# design.net
KiCad netlist of a schematic drawn in EAGLE
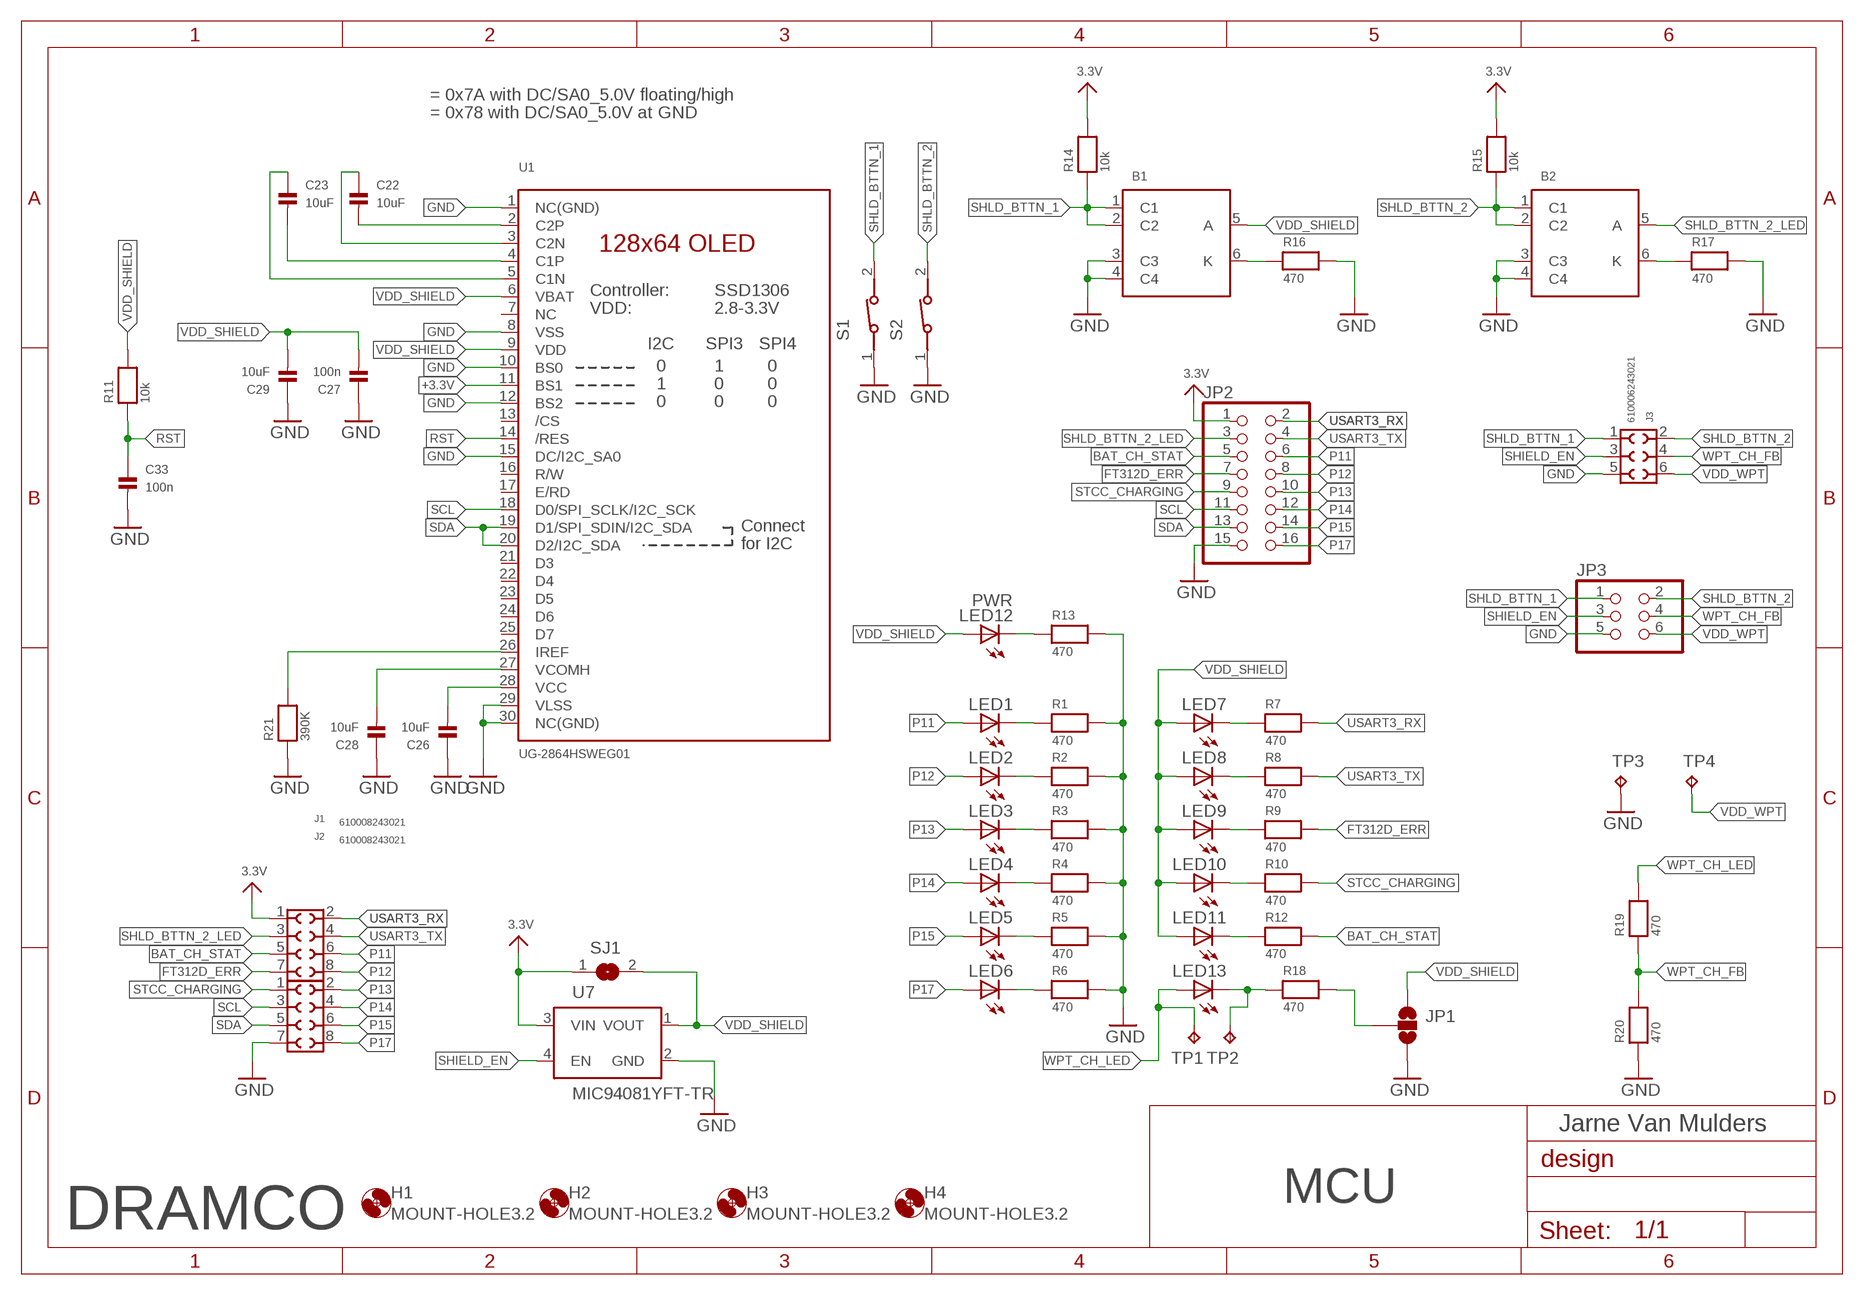
[diagram p0: schematic, sheet 1]

(export (version "E")
  (design (tool "Eeschema 10.0.6"))
  (components
    (comp (ref "B1")
      (value "TS121273")
      (footprint "eagle-import:TS121273")
      (libsource (lib "eagle-import") (part "TS121273"))
    )
    (comp (ref "B2")
      (value "TS121273")
      (footprint "eagle-import:TS121273")
      (libsource (lib "eagle-import") (part "TS121273"))
    )
    (comp (ref "C22")
      (value "10uF")
      (footprint "eagle-import:0805")
      (libsource (lib "eagle-import") (part "CAP_CERAMIC0805"))
    )
    (comp (ref "C23")
      (value "10uF")
      (footprint "eagle-import:0805")
      (libsource (lib "eagle-import") (part "CAP_CERAMIC0805"))
    )
    (comp (ref "C26")
      (value "10uF")
      (footprint "eagle-import:0805")
      (libsource (lib "eagle-import") (part "CAP_CERAMIC0805"))
    )
    (comp (ref "C27")
      (value "100n")
      (footprint "eagle-import:0603")
      (libsource (lib "eagle-import") (part "CAP_CERAMIC0603"))
    )
    (comp (ref "C28")
      (value "10uF")
      (footprint "eagle-import:0805")
      (libsource (lib "eagle-import") (part "CAP_CERAMIC0805"))
    )
    (comp (ref "C29")
      (value "10uF")
      (footprint "eagle-import:0805")
      (libsource (lib "eagle-import") (part "CAP_CERAMIC0805"))
    )
    (comp (ref "C33")
      (value "100n")
      (footprint "eagle-import:0603")
      (libsource (lib "eagle-import") (part "CAP_CERAMIC0603"))
    )
    (comp (ref "H1")
      (value "MOUNT-HOLE3.2")
      (footprint "eagle-import:3,2")
      (libsource (lib "eagle-import") (part "MOUNT-HOLE3.2"))
    )
    (comp (ref "H2")
      (value "MOUNT-HOLE3.2")
      (footprint "eagle-import:3,2")
      (libsource (lib "eagle-import") (part "MOUNT-HOLE3.2"))
    )
    (comp (ref "H3")
      (value "MOUNT-HOLE3.2")
      (footprint "eagle-import:3,2")
      (libsource (lib "eagle-import") (part "MOUNT-HOLE3.2"))
    )
    (comp (ref "H4")
      (value "MOUNT-HOLE3.2")
      (footprint "eagle-import:3,2")
      (libsource (lib "eagle-import") (part "MOUNT-HOLE3.2"))
    )
    (comp (ref "J1")
      (value "610008243021")
      (footprint "eagle-import:610008243021")
      (libsource (lib "eagle-import") (part "6100XX243021_610008243021"))
    )
    (comp (ref "J2")
      (value "610008243021")
      (footprint "eagle-import:610008243021")
      (libsource (lib "eagle-import") (part "6100XX243021_610008243021"))
    )
    (comp (ref "J3")
      (value "610006243021")
      (footprint "eagle-import:610006243021")
      (libsource (lib "eagle-import") (part "6100XX243021_610006243021"))
    )
    (comp (ref "JP1")
      (value "JUMPER-SMT_3_NO_NO-SILK")
      (footprint "eagle-import:SMT-JUMPER_3_NO_NO-SILK")
      (libsource (lib "eagle-import") (part "JUMPER-SMT_3_NO_NO-SILK"))
    )
    (comp (ref "JP2")
      (value "HEADER-2X8")
      (footprint "eagle-import:2X08")
      (libsource (lib "eagle-import") (part "HEADER-2X8"))
    )
    (comp (ref "JP3")
      (value "HEADER-2X3")
      (footprint "eagle-import:2X03_ROUND_70MIL")
      (libsource (lib "eagle-import") (part "HEADER-2X3"))
    )
    (comp (ref "LED1")
      (value "LED3MM")
      (footprint "eagle-import:LED3MM")
      (libsource (lib "eagle-import") (part "LED3MM"))
    )
    (comp (ref "LED2")
      (value "LED3MM")
      (footprint "eagle-import:LED3MM")
      (libsource (lib "eagle-import") (part "LED3MM"))
    )
    (comp (ref "LED3")
      (value "LED3MM")
      (footprint "eagle-import:LED3MM")
      (libsource (lib "eagle-import") (part "LED3MM"))
    )
    (comp (ref "LED4")
      (value "LED3MM")
      (footprint "eagle-import:LED3MM")
      (libsource (lib "eagle-import") (part "LED3MM"))
    )
    (comp (ref "LED5")
      (value "LED3MM")
      (footprint "eagle-import:LED3MM")
      (libsource (lib "eagle-import") (part "LED3MM"))
    )
    (comp (ref "LED6")
      (value "LED3MM")
      (footprint "eagle-import:LED3MM")
      (libsource (lib "eagle-import") (part "LED3MM"))
    )
    (comp (ref "LED7")
      (value "LED3MM")
      (footprint "eagle-import:LED3MM")
      (libsource (lib "eagle-import") (part "LED3MM"))
    )
    (comp (ref "LED8")
      (value "LED3MM")
      (footprint "eagle-import:LED3MM")
      (libsource (lib "eagle-import") (part "LED3MM"))
    )
    (comp (ref "LED9")
      (value "LED3MM")
      (footprint "eagle-import:LED3MM")
      (libsource (lib "eagle-import") (part "LED3MM"))
    )
    (comp (ref "LED10")
      (value "LED3MM")
      (footprint "eagle-import:LED3MM")
      (libsource (lib "eagle-import") (part "LED3MM"))
    )
    (comp (ref "LED11")
      (value "LED3MM")
      (footprint "eagle-import:LED3MM")
      (libsource (lib "eagle-import") (part "LED3MM"))
    )
    (comp (ref "LED12")
      (value "PWR")
      (footprint "eagle-import:LED3MM")
      (libsource (lib "eagle-import") (part "LED3MM"))
    )
    (comp (ref "LED13")
      (value "LED3MM")
      (footprint "eagle-import:LED3MM")
      (libsource (lib "eagle-import") (part "LED3MM"))
    )
    (comp (ref "R1")
      (value "470")
      (footprint "eagle-import:0603")
      (libsource (lib "eagle-import") (part "RESISTOR0603"))
    )
    (comp (ref "R2")
      (value "470")
      (footprint "eagle-import:0603")
      (libsource (lib "eagle-import") (part "RESISTOR0603"))
    )
    (comp (ref "R3")
      (value "470")
      (footprint "eagle-import:0603")
      (libsource (lib "eagle-import") (part "RESISTOR0603"))
    )
    (comp (ref "R4")
      (value "470")
      (footprint "eagle-import:0603")
      (libsource (lib "eagle-import") (part "RESISTOR0603"))
    )
    (comp (ref "R5")
      (value "470")
      (footprint "eagle-import:0603")
      (libsource (lib "eagle-import") (part "RESISTOR0603"))
    )
    (comp (ref "R6")
      (value "470")
      (footprint "eagle-import:0603")
      (libsource (lib "eagle-import") (part "RESISTOR0603"))
    )
    (comp (ref "R7")
      (value "470")
      (footprint "eagle-import:0603")
      (libsource (lib "eagle-import") (part "RESISTOR0603"))
    )
    (comp (ref "R8")
      (value "470")
      (footprint "eagle-import:0603")
      (libsource (lib "eagle-import") (part "RESISTOR0603"))
    )
    (comp (ref "R9")
      (value "470")
      (footprint "eagle-import:0603")
      (libsource (lib "eagle-import") (part "RESISTOR0603"))
    )
    (comp (ref "R10")
      (value "470")
      (footprint "eagle-import:0603")
      (libsource (lib "eagle-import") (part "RESISTOR0603"))
    )
    (comp (ref "R11")
      (value "10k")
      (footprint "eagle-import:0805")
      (libsource (lib "eagle-import") (part "RESISTOR0805"))
    )
    (comp (ref "R12")
      (value "470")
      (footprint "eagle-import:0603")
      (libsource (lib "eagle-import") (part "RESISTOR0603"))
    )
    (comp (ref "R13")
      (value "470")
      (footprint "eagle-import:0603")
      (libsource (lib "eagle-import") (part "RESISTOR0603"))
    )
    (comp (ref "R14")
      (value "10k")
      (footprint "eagle-import:0603")
      (libsource (lib "eagle-import") (part "RESISTOR0603"))
    )
    (comp (ref "R15")
      (value "10k")
      (footprint "eagle-import:0603")
      (libsource (lib "eagle-import") (part "RESISTOR0603"))
    )
    (comp (ref "R16")
      (value "470")
      (footprint "eagle-import:0603")
      (libsource (lib "eagle-import") (part "RESISTOR0603"))
    )
    (comp (ref "R17")
      (value "470")
      (footprint "eagle-import:0603")
      (libsource (lib "eagle-import") (part "RESISTOR0603"))
    )
    (comp (ref "R18")
      (value "470")
      (footprint "eagle-import:0603")
      (libsource (lib "eagle-import") (part "RESISTOR0603"))
    )
    (comp (ref "R19")
      (value "470")
      (footprint "eagle-import:0603")
      (libsource (lib "eagle-import") (part "RESISTOR0603"))
    )
    (comp (ref "R20")
      (value "470")
      (footprint "eagle-import:0603")
      (libsource (lib "eagle-import") (part "RESISTOR0603"))
    )
    (comp (ref "R21")
      (value "390K")
      (footprint "eagle-import:0805")
      (libsource (lib "eagle-import") (part "RESISTOR0805"))
    )
    (comp (ref "S1")
      (value "434111043826")
      (footprint "eagle-import:434111043826")
      (libsource (lib "eagle-import") (part "434111043826"))
    )
    (comp (ref "S2")
      (value "434111043826")
      (footprint "eagle-import:434111043826")
      (libsource (lib "eagle-import") (part "434111043826"))
    )
    (comp (ref "SJ1")
      (value "SOLDERJUMPERREFLOW")
      (footprint "eagle-import:SOLDERJUMPER_REFLOW")
      (libsource (lib "eagle-import") (part "SOLDERJUMPERREFLOW"))
    )
    (comp (ref "TP1")
      (value "TPTP20SQ")
      (footprint "eagle-import:TP20SQ")
      (libsource (lib "eagle-import") (part "TPTP20SQ"))
    )
    (comp (ref "TP2")
      (value "TPTP20SQ")
      (footprint "eagle-import:TP20SQ")
      (libsource (lib "eagle-import") (part "TPTP20SQ"))
    )
    (comp (ref "TP3")
      (value "TPTP20SQ")
      (footprint "eagle-import:TP20SQ")
      (libsource (lib "eagle-import") (part "TPTP20SQ"))
    )
    (comp (ref "TP4")
      (value "TPTP20SQ")
      (footprint "eagle-import:TP20SQ")
      (libsource (lib "eagle-import") (part "TPTP20SQ"))
    )
    (comp (ref "U1")
      (value "UG-2864HSWEG01")
      (footprint "eagle-import:UG-2864HSWEG01_0.96IN_WRAPAROUND")
      (libsource (lib "eagle-import") (part "DISP_OLED_UG-2864HSWEG010.96{dblquote}"))
    )
    (comp (ref "U7")
      (value "MIC94081YFT-TR")
      (footprint "eagle-import:IC_MIC94081YFT-TR")
      (fields (field (name "MF") "Microchip"))
      (libsource (lib "eagle-import") (part "MIC94081YFT-TR"))
    )
  )
  (nets
    (net (code "1") (name "+3.3V") (class "Default")
      (node (ref "U1") (pin "11") (pinfunction "BS1_11") (pintype "input"))
    )
    (net (code "2") (name "3.3V") (class "Default")
      (node (ref "J2") (pin "1") (pinfunction "1_1") (pintype "passive"))
      (node (ref "JP2") (pin "1") (pinfunction "1_1") (pintype "passive"))
      (node (ref "R14") (pin "2") (pinfunction "2_2") (pintype "passive"))
      (node (ref "R15") (pin "2") (pinfunction "2_2") (pintype "passive"))
      (node (ref "SJ1") (pin "1") (pinfunction "1_1") (pintype "passive"))
      (node (ref "U7") (pin "3") (pinfunction "VIN_3") (pintype "input"))
    )
    (net (code "3") (name "BAT_CH_STAT") (class "Default")
      (node (ref "J2") (pin "5") (pinfunction "5_5") (pintype "passive"))
      (node (ref "JP2") (pin "5") (pinfunction "5_5") (pintype "passive"))
      (node (ref "R12") (pin "2") (pinfunction "2_2") (pintype "passive"))
    )
    (net (code "4") (name "FT312D_ERR") (class "Default")
      (node (ref "J2") (pin "7") (pinfunction "7_7") (pintype "passive"))
      (node (ref "JP2") (pin "7") (pinfunction "7_7") (pintype "passive"))
      (node (ref "R9") (pin "2") (pinfunction "2_2") (pintype "passive"))
    )
    (net (code "5") (name "GND") (class "Default")
      (node (ref "B1") (pin "3") (pinfunction "C3_3") (pintype "bidirectional"))
      (node (ref "B1") (pin "4") (pinfunction "C4_4") (pintype "bidirectional"))
      (node (ref "B2") (pin "3") (pinfunction "C3_3") (pintype "bidirectional"))
      (node (ref "B2") (pin "4") (pinfunction "C4_4") (pintype "bidirectional"))
      (node (ref "C26") (pin "1") (pinfunction "P$1_1") (pintype "passive"))
      (node (ref "C27") (pin "1") (pinfunction "P$1_1") (pintype "passive"))
      (node (ref "C28") (pin "1") (pinfunction "P$1_1") (pintype "passive"))
      (node (ref "C29") (pin "1") (pinfunction "P$1_1") (pintype "passive"))
      (node (ref "C33") (pin "2") (pinfunction "P$2_2") (pintype "passive"))
      (node (ref "J1") (pin "7") (pinfunction "7_7") (pintype "passive"))
      (node (ref "J3") (pin "5") (pinfunction "5_5") (pintype "passive"))
      (node (ref "JP1") (pin "3") (pinfunction "3_3") (pintype "passive"))
      (node (ref "JP2") (pin "15") (pinfunction "15_15") (pintype "passive"))
      (node (ref "JP3") (pin "5") (pinfunction "5_5") (pintype "passive"))
      (node (ref "R1") (pin "2") (pinfunction "2_2") (pintype "passive"))
      (node (ref "R13") (pin "2") (pinfunction "2_2") (pintype "passive"))
      (node (ref "R16") (pin "2") (pinfunction "2_2") (pintype "passive"))
      (node (ref "R17") (pin "2") (pinfunction "2_2") (pintype "passive"))
      (node (ref "R2") (pin "2") (pinfunction "2_2") (pintype "passive"))
      (node (ref "R20") (pin "1") (pinfunction "1_1") (pintype "passive"))
      (node (ref "R21") (pin "1") (pinfunction "1_1") (pintype "passive"))
      (node (ref "R3") (pin "2") (pinfunction "2_2") (pintype "passive"))
      (node (ref "R4") (pin "2") (pinfunction "2_2") (pintype "passive"))
      (node (ref "R5") (pin "2") (pinfunction "2_2") (pintype "passive"))
      (node (ref "R6") (pin "2") (pinfunction "2_2") (pintype "passive"))
      (node (ref "S1") (pin "1") (pinfunction "1_1") (pintype "passive"))
      (node (ref "S2") (pin "1") (pinfunction "1_1") (pintype "passive"))
      (node (ref "TP3") (pin "TP") (pinfunction "TP_TP") (pintype "input"))
      (node (ref "U1") (pin "1") (pinfunction "NC(GND)_1") (pintype "input"))
      (node (ref "U1") (pin "10") (pinfunction "BS0_10") (pintype "input"))
      (node (ref "U1") (pin "12") (pinfunction "BS2_12") (pintype "input"))
      (node (ref "U1") (pin "15") (pinfunction "DC/I2C_SA0_15") (pintype "input"))
      (node (ref "U1") (pin "29") (pinfunction "VLSS_29") (pintype "power_in"))
      (node (ref "U1") (pin "30") (pinfunction "NC(GND)_30") (pintype "input"))
      (node (ref "U1") (pin "8") (pinfunction "VSS_8") (pintype "power_in"))
      (node (ref "U7") (pin "2") (pinfunction "GND_2") (pintype "power_in"))
    )
    (net (code "6") (name "Net-(B1-K)") (class "Default")
      (node (ref "B1") (pin "6") (pinfunction "K_6") (pintype "bidirectional"))
      (node (ref "R16") (pin "1") (pinfunction "1_1") (pintype "passive"))
    )
    (net (code "7") (name "Net-(B2-K)") (class "Default")
      (node (ref "B2") (pin "6") (pinfunction "K_6") (pintype "bidirectional"))
      (node (ref "R17") (pin "1") (pinfunction "1_1") (pintype "passive"))
    )
    (net (code "8") (name "Net-(C22-P$1)") (class "Default")
      (node (ref "C22") (pin "1") (pinfunction "P$1_1") (pintype "passive"))
      (node (ref "U1") (pin "3") (pinfunction "C2N_3") (pintype "input"))
    )
    (net (code "9") (name "Net-(C22-P$2)") (class "Default")
      (node (ref "C22") (pin "2") (pinfunction "P$2_2") (pintype "passive"))
      (node (ref "U1") (pin "2") (pinfunction "C2P_2") (pintype "input"))
    )
    (net (code "10") (name "Net-(C23-P$1)") (class "Default")
      (node (ref "C23") (pin "1") (pinfunction "P$1_1") (pintype "passive"))
      (node (ref "U1") (pin "5") (pinfunction "C1N_5") (pintype "input"))
    )
    (net (code "11") (name "Net-(C23-P$2)") (class "Default")
      (node (ref "C23") (pin "2") (pinfunction "P$2_2") (pintype "passive"))
      (node (ref "U1") (pin "4") (pinfunction "C1P_4") (pintype "input"))
    )
    (net (code "12") (name "Net-(C26-P$2)") (class "Default")
      (node (ref "C26") (pin "2") (pinfunction "P$2_2") (pintype "passive"))
      (node (ref "U1") (pin "28") (pinfunction "VCC_28") (pintype "power_in"))
    )
    (net (code "13") (name "Net-(C28-P$2)") (class "Default")
      (node (ref "C28") (pin "2") (pinfunction "P$2_2") (pintype "passive"))
      (node (ref "U1") (pin "27") (pinfunction "VCOMH_27") (pintype "output"))
    )
    (net (code "14") (name "Net-(JP1-Pad2)") (class "Default")
      (node (ref "JP1") (pin "2") (pinfunction "2_2") (pintype "passive"))
      (node (ref "R18") (pin "2") (pinfunction "2_2") (pintype "passive"))
    )
    (net (code "15") (name "Net-(LED1-C)") (class "Default")
      (node (ref "LED1") (pin "K") (pinfunction "C_K") (pintype "passive"))
      (node (ref "R1") (pin "1") (pinfunction "1_1") (pintype "passive"))
    )
    (net (code "16") (name "Net-(LED2-C)") (class "Default")
      (node (ref "LED2") (pin "K") (pinfunction "C_K") (pintype "passive"))
      (node (ref "R2") (pin "1") (pinfunction "1_1") (pintype "passive"))
    )
    (net (code "17") (name "Net-(LED3-C)") (class "Default")
      (node (ref "LED3") (pin "K") (pinfunction "C_K") (pintype "passive"))
      (node (ref "R3") (pin "1") (pinfunction "1_1") (pintype "passive"))
    )
    (net (code "18") (name "Net-(LED4-C)") (class "Default")
      (node (ref "LED4") (pin "K") (pinfunction "C_K") (pintype "passive"))
      (node (ref "R4") (pin "1") (pinfunction "1_1") (pintype "passive"))
    )
    (net (code "19") (name "Net-(LED5-C)") (class "Default")
      (node (ref "LED5") (pin "K") (pinfunction "C_K") (pintype "passive"))
      (node (ref "R5") (pin "1") (pinfunction "1_1") (pintype "passive"))
    )
    (net (code "20") (name "Net-(LED6-C)") (class "Default")
      (node (ref "LED6") (pin "K") (pinfunction "C_K") (pintype "passive"))
      (node (ref "R6") (pin "1") (pinfunction "1_1") (pintype "passive"))
    )
    (net (code "21") (name "Net-(LED7-C)") (class "Default")
      (node (ref "LED7") (pin "K") (pinfunction "C_K") (pintype "passive"))
      (node (ref "R7") (pin "1") (pinfunction "1_1") (pintype "passive"))
    )
    (net (code "22") (name "Net-(LED8-C)") (class "Default")
      (node (ref "LED8") (pin "K") (pinfunction "C_K") (pintype "passive"))
      (node (ref "R8") (pin "1") (pinfunction "1_1") (pintype "passive"))
    )
    (net (code "23") (name "Net-(LED9-C)") (class "Default")
      (node (ref "LED9") (pin "K") (pinfunction "C_K") (pintype "passive"))
      (node (ref "R9") (pin "1") (pinfunction "1_1") (pintype "passive"))
    )
    (net (code "24") (name "Net-(LED10-C)") (class "Default")
      (node (ref "LED10") (pin "K") (pinfunction "C_K") (pintype "passive"))
      (node (ref "R10") (pin "1") (pinfunction "1_1") (pintype "passive"))
    )
    (net (code "25") (name "Net-(LED11-C)") (class "Default")
      (node (ref "LED11") (pin "K") (pinfunction "C_K") (pintype "passive"))
      (node (ref "R12") (pin "1") (pinfunction "1_1") (pintype "passive"))
    )
    (net (code "26") (name "Net-(LED12-C)") (class "Default")
      (node (ref "LED12") (pin "K") (pinfunction "C_K") (pintype "passive"))
      (node (ref "R13") (pin "1") (pinfunction "1_1") (pintype "passive"))
    )
    (net (code "27") (name "Net-(LED13-C)") (class "Default")
      (node (ref "LED13") (pin "K") (pinfunction "C_K") (pintype "passive"))
      (node (ref "R18") (pin "1") (pinfunction "1_1") (pintype "passive"))
      (node (ref "TP2") (pin "TP") (pinfunction "TP_TP") (pintype "input"))
    )
    (net (code "28") (name "Net-(U1-IREF)") (class "Default")
      (node (ref "R21") (pin "2") (pinfunction "2_2") (pintype "passive"))
      (node (ref "U1") (pin "26") (pinfunction "IREF_26") (pintype "input"))
    )
    (net (code "29") (name "P11") (class "Default")
      (node (ref "J2") (pin "6") (pinfunction "6_6") (pintype "passive"))
      (node (ref "JP2") (pin "6") (pinfunction "6_6") (pintype "passive"))
      (node (ref "LED1") (pin "A") (pinfunction "A_A") (pintype "passive"))
    )
    (net (code "30") (name "P12") (class "Default")
      (node (ref "J2") (pin "8") (pinfunction "8_8") (pintype "passive"))
      (node (ref "JP2") (pin "8") (pinfunction "8_8") (pintype "passive"))
      (node (ref "LED2") (pin "A") (pinfunction "A_A") (pintype "passive"))
    )
    (net (code "31") (name "P13") (class "Default")
      (node (ref "J1") (pin "2") (pinfunction "2_2") (pintype "passive"))
      (node (ref "JP2") (pin "10") (pinfunction "10_10") (pintype "passive"))
      (node (ref "LED3") (pin "A") (pinfunction "A_A") (pintype "passive"))
    )
    (net (code "32") (name "P14") (class "Default")
      (node (ref "J1") (pin "4") (pinfunction "4_4") (pintype "passive"))
      (node (ref "JP2") (pin "12") (pinfunction "12_12") (pintype "passive"))
      (node (ref "LED4") (pin "A") (pinfunction "A_A") (pintype "passive"))
    )
    (net (code "33") (name "P15") (class "Default")
      (node (ref "J1") (pin "6") (pinfunction "6_6") (pintype "passive"))
      (node (ref "JP2") (pin "14") (pinfunction "14_14") (pintype "passive"))
      (node (ref "LED5") (pin "A") (pinfunction "A_A") (pintype "passive"))
    )
    (net (code "34") (name "P17") (class "Default")
      (node (ref "J1") (pin "8") (pinfunction "8_8") (pintype "passive"))
      (node (ref "JP2") (pin "16") (pinfunction "16_16") (pintype "passive"))
      (node (ref "LED6") (pin "A") (pinfunction "A_A") (pintype "passive"))
    )
    (net (code "35") (name "RST") (class "Default")
      (node (ref "C33") (pin "1") (pinfunction "P$1_1") (pintype "passive"))
      (node (ref "R11") (pin "1") (pinfunction "1_1") (pintype "passive"))
      (node (ref "U1") (pin "14") (pinfunction "/RES_14") (pintype "input"))
    )
    (net (code "36") (name "SCL") (class "Default")
      (node (ref "J1") (pin "3") (pinfunction "3_3") (pintype "passive"))
      (node (ref "JP2") (pin "11") (pinfunction "11_11") (pintype "passive"))
      (node (ref "U1") (pin "18") (pinfunction "D0/SPI_SCLK/I2C_SCK_18") (pintype "bidirectional"))
    )
    (net (code "37") (name "SDA") (class "Default")
      (node (ref "J1") (pin "5") (pinfunction "5_5") (pintype "passive"))
      (node (ref "JP2") (pin "13") (pinfunction "13_13") (pintype "passive"))
      (node (ref "U1") (pin "19") (pinfunction "D1/SPI_SDIN/I2C_SDA_19") (pintype "bidirectional"))
      (node (ref "U1") (pin "20") (pinfunction "D2/I2C_SDA_20") (pintype "bidirectional"))
    )
    (net (code "38") (name "SHIELD_EN") (class "Default")
      (node (ref "J3") (pin "3") (pinfunction "3_3") (pintype "passive"))
      (node (ref "JP3") (pin "3") (pinfunction "3_3") (pintype "passive"))
      (node (ref "U7") (pin "4") (pinfunction "EN_4") (pintype "input"))
    )
    (net (code "39") (name "SHLD_BTTN_1") (class "Default")
      (node (ref "B1") (pin "1") (pinfunction "C1_1") (pintype "bidirectional"))
      (node (ref "B1") (pin "2") (pinfunction "C2_2") (pintype "bidirectional"))
      (node (ref "J3") (pin "1") (pinfunction "1_1") (pintype "passive"))
      (node (ref "JP3") (pin "1") (pinfunction "1_1") (pintype "passive"))
      (node (ref "R14") (pin "1") (pinfunction "1_1") (pintype "passive"))
      (node (ref "S1") (pin "2") (pinfunction "2_2") (pintype "passive"))
    )
    (net (code "40") (name "SHLD_BTTN_2") (class "Default")
      (node (ref "B2") (pin "1") (pinfunction "C1_1") (pintype "bidirectional"))
      (node (ref "B2") (pin "2") (pinfunction "C2_2") (pintype "bidirectional"))
      (node (ref "J3") (pin "2") (pinfunction "2_2") (pintype "passive"))
      (node (ref "JP3") (pin "2") (pinfunction "2_2") (pintype "passive"))
      (node (ref "R15") (pin "1") (pinfunction "1_1") (pintype "passive"))
      (node (ref "S2") (pin "2") (pinfunction "2_2") (pintype "passive"))
    )
    (net (code "41") (name "SHLD_BTTN_2_LED") (class "Default")
      (node (ref "B2") (pin "5") (pinfunction "A_5") (pintype "bidirectional"))
      (node (ref "J2") (pin "3") (pinfunction "3_3") (pintype "passive"))
      (node (ref "JP2") (pin "3") (pinfunction "3_3") (pintype "passive"))
    )
    (net (code "42") (name "STCC_CHARGING") (class "Default")
      (node (ref "J1") (pin "1") (pinfunction "1_1") (pintype "passive"))
      (node (ref "JP2") (pin "9") (pinfunction "9_9") (pintype "passive"))
      (node (ref "R10") (pin "2") (pinfunction "2_2") (pintype "passive"))
    )
    (net (code "43") (name "USART3_RX") (class "Default")
      (node (ref "J2") (pin "2") (pinfunction "2_2") (pintype "passive"))
      (node (ref "JP2") (pin "2") (pinfunction "2_2") (pintype "passive"))
      (node (ref "R7") (pin "2") (pinfunction "2_2") (pintype "passive"))
    )
    (net (code "44") (name "USART3_TX") (class "Default")
      (node (ref "J2") (pin "4") (pinfunction "4_4") (pintype "passive"))
      (node (ref "JP2") (pin "4") (pinfunction "4_4") (pintype "passive"))
      (node (ref "R8") (pin "2") (pinfunction "2_2") (pintype "passive"))
    )
    (net (code "45") (name "VDD_SHIELD") (class "Default")
      (node (ref "B1") (pin "5") (pinfunction "A_5") (pintype "bidirectional"))
      (node (ref "C27") (pin "2") (pinfunction "P$2_2") (pintype "passive"))
      (node (ref "C29") (pin "2") (pinfunction "P$2_2") (pintype "passive"))
      (node (ref "JP1") (pin "1") (pinfunction "1_1") (pintype "passive"))
      (node (ref "LED10") (pin "A") (pinfunction "A_A") (pintype "passive"))
      (node (ref "LED11") (pin "A") (pinfunction "A_A") (pintype "passive"))
      (node (ref "LED12") (pin "A") (pinfunction "A_A") (pintype "passive"))
      (node (ref "LED7") (pin "A") (pinfunction "A_A") (pintype "passive"))
      (node (ref "LED8") (pin "A") (pinfunction "A_A") (pintype "passive"))
      (node (ref "LED9") (pin "A") (pinfunction "A_A") (pintype "passive"))
      (node (ref "R11") (pin "2") (pinfunction "2_2") (pintype "passive"))
      (node (ref "SJ1") (pin "2") (pinfunction "2_2") (pintype "passive"))
      (node (ref "U1") (pin "6") (pinfunction "VBAT_6") (pintype "input"))
      (node (ref "U1") (pin "9") (pinfunction "VDD_9") (pintype "power_in"))
      (node (ref "U7") (pin "1") (pinfunction "VOUT_1") (pintype "output"))
    )
    (net (code "46") (name "VDD_WPT") (class "Default")
      (node (ref "J3") (pin "6") (pinfunction "6_6") (pintype "passive"))
      (node (ref "JP3") (pin "6") (pinfunction "6_6") (pintype "passive"))
      (node (ref "TP4") (pin "TP") (pinfunction "TP_TP") (pintype "input"))
    )
    (net (code "47") (name "WPT_CH_FB") (class "Default")
      (node (ref "J3") (pin "4") (pinfunction "4_4") (pintype "passive"))
      (node (ref "JP3") (pin "4") (pinfunction "4_4") (pintype "passive"))
      (node (ref "R19") (pin "1") (pinfunction "1_1") (pintype "passive"))
      (node (ref "R20") (pin "2") (pinfunction "2_2") (pintype "passive"))
    )
    (net (code "48") (name "WPT_CH_LED") (class "Default")
      (node (ref "LED13") (pin "A") (pinfunction "A_A") (pintype "passive"))
      (node (ref "R19") (pin "2") (pinfunction "2_2") (pintype "passive"))
      (node (ref "TP1") (pin "TP") (pinfunction "TP_TP") (pintype "input"))
    )
    (net (code "49") (name "unconnected-(U1-D3-Pad21)") (class "Default")
      (node (ref "U1") (pin "21") (pinfunction "D3_21") (pintype "bidirectional"))
    )
    (net (code "50") (name "unconnected-(U1-D4-Pad22)") (class "Default")
      (node (ref "U1") (pin "22") (pinfunction "D4_22") (pintype "bidirectional"))
    )
    (net (code "51") (name "unconnected-(U1-D5-Pad23)") (class "Default")
      (node (ref "U1") (pin "23") (pinfunction "D5_23") (pintype "bidirectional"))
    )
    (net (code "52") (name "unconnected-(U1-D6-Pad24)") (class "Default")
      (node (ref "U1") (pin "24") (pinfunction "D6_24") (pintype "bidirectional"))
    )
    (net (code "53") (name "unconnected-(U1-D7-Pad25)") (class "Default")
      (node (ref "U1") (pin "25") (pinfunction "D7_25") (pintype "bidirectional"))
    )
    (net (code "54") (name "unconnected-(U1-E{slash}RD-Pad17)") (class "Default")
      (node (ref "U1") (pin "17") (pinfunction "E/RD_17") (pintype "input"))
    )
    (net (code "55") (name "unconnected-(U1-NC-Pad7)") (class "Default")
      (node (ref "U1") (pin "7") (pinfunction "NC_7") (pintype "no_connect"))
    )
    (net (code "56") (name "unconnected-(U1-R{slash}W-Pad16)") (class "Default")
      (node (ref "U1") (pin "16") (pinfunction "R/W_16") (pintype "input"))
    )
    (net (code "57") (name "unconnected-(U1-{slash}CS-Pad13)") (class "Default")
      (node (ref "U1") (pin "13") (pinfunction "/CS_13") (pintype "input"))
    )
  )
)
